# Mezz2.net
KiCad netlist of a schematic drawn in Altium Designer
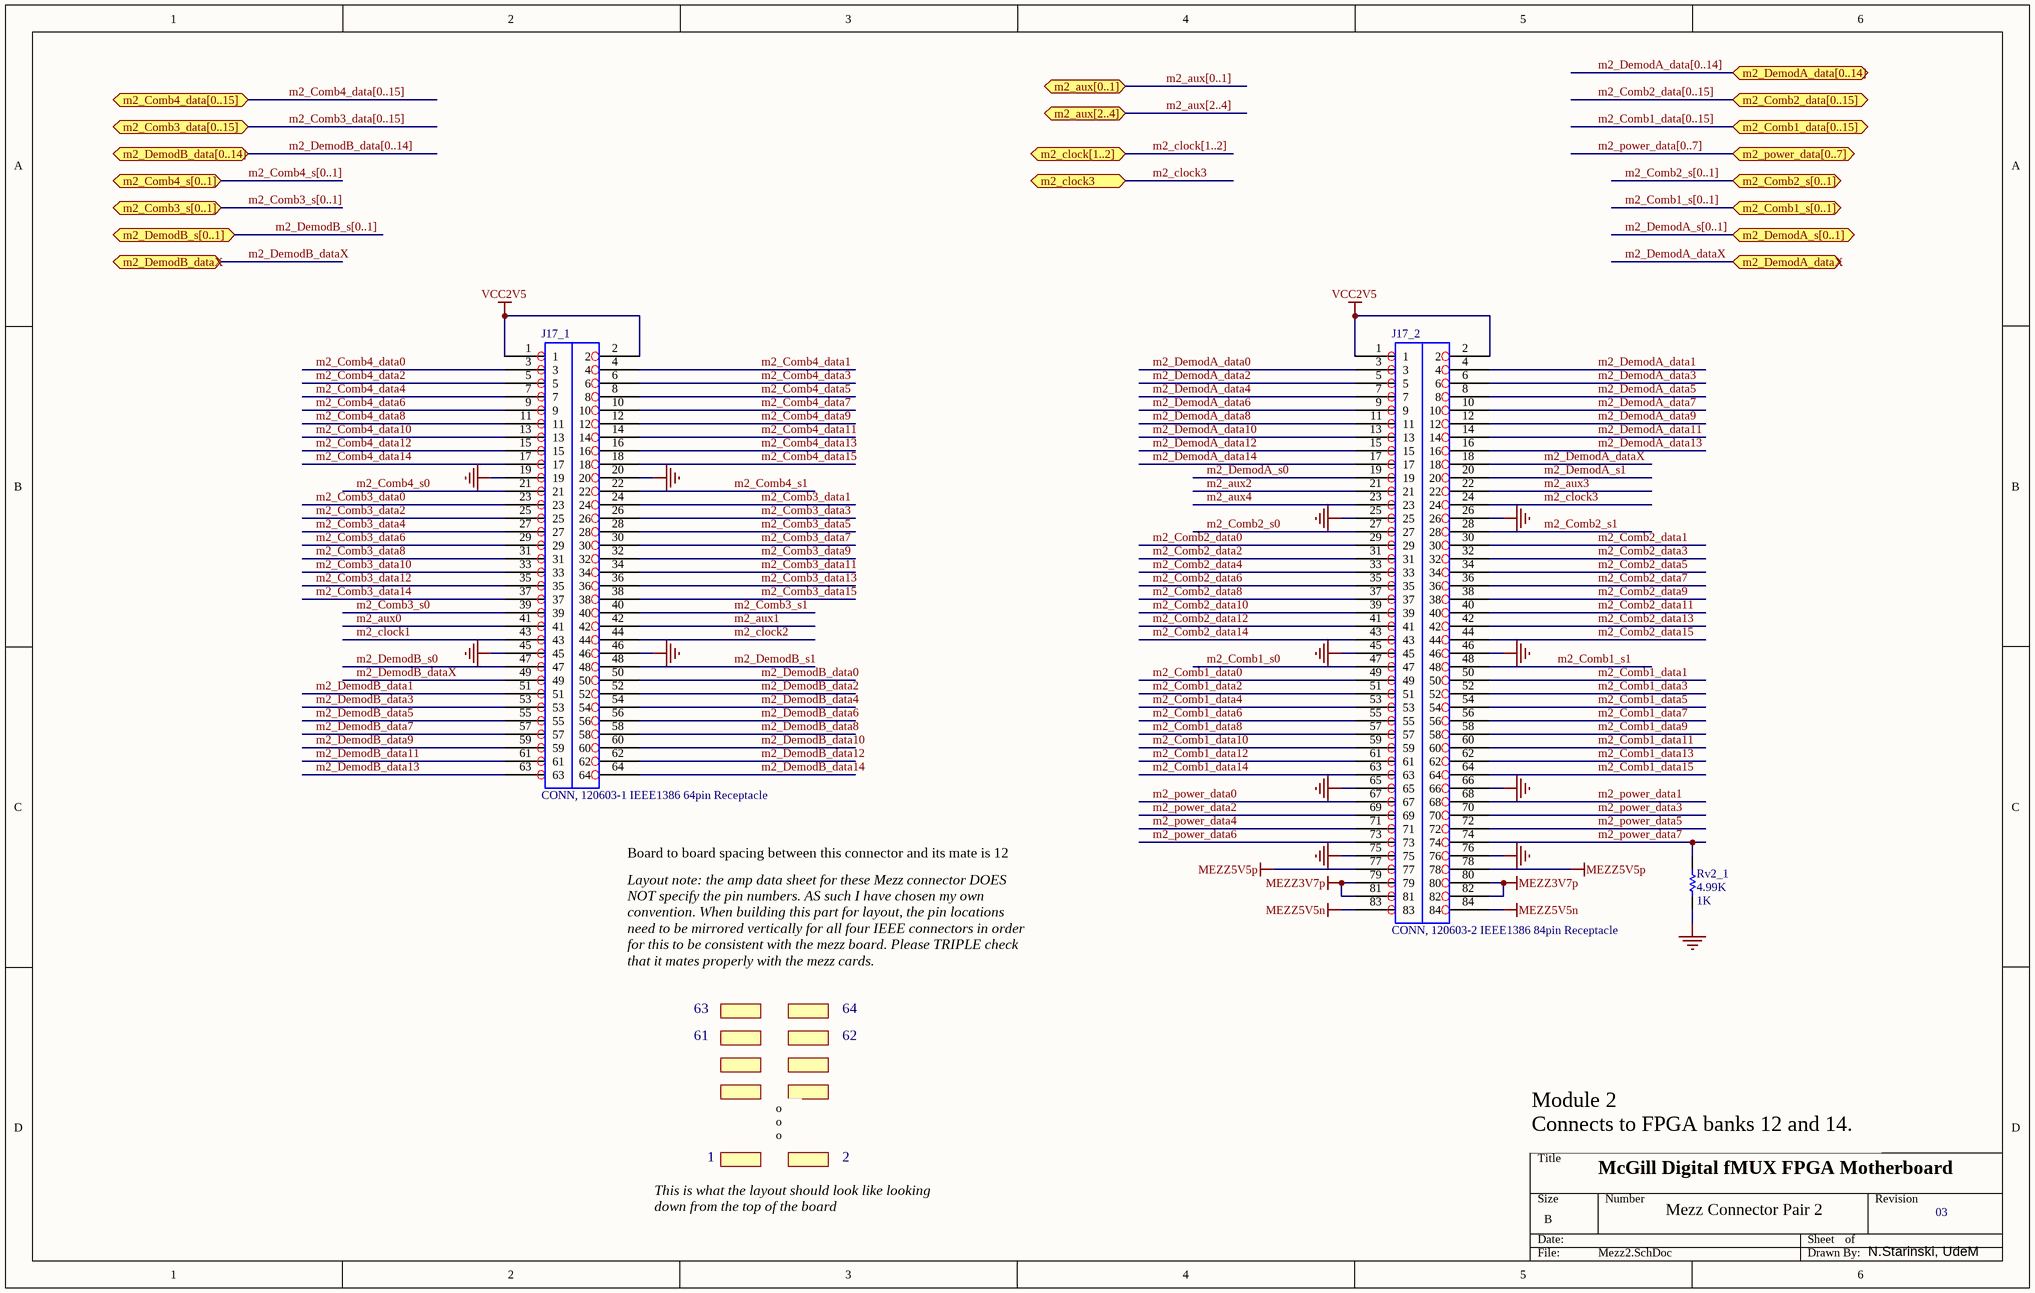
[diagram p0: Mezz2.SchDoc]

(export (version "E")
  (design (tool "Eeschema 10.0.6"))
  (components
    (comp (ref "J17_1")
      (value "CONN, 120603-1 IEEE1386 64pin Receptacle")
      (footprint "120603-1")
      (description "1.0mm FH (IEEE1386) 64-pin Connector")
      (libsource (lib "IEEE1386") (part "120603-1"))
    )
    (comp (ref "J17_2")
      (value "CONN, 120603-2 IEEE1386 84pin Receptacle")
      (footprint "120603-2")
      (description "1.0mm FH (IEEE1386) 84-pin Connector")
      (libsource (lib "IEEE1386") (part "120603-2"))
    )
    (comp (ref "Rv2_1")
      (value "4.99K")
      (footprint "1608[0603]")
      (description "Semiconductor Resistor")
      (fields (field (name "ALTIUM_VALUE") "1K") (field (name "PUBLISHER") "Altium Limited"))
      (libsource (lib "Miscellaneous Devices") (part "Res Semi"))
    )
  )
  (nets
    (net (code "1") (name "/m2_Comb1_data0") (class "Default")
      (node (ref "J17_2") (pin "49") (pinfunction "49_49") (pintype "passive"))
    )
    (net (code "2") (name "/m2_Comb1_data1") (class "Default")
      (node (ref "J17_2") (pin "50") (pinfunction "50_50") (pintype "passive"))
    )
    (net (code "3") (name "/m2_Comb1_data2") (class "Default")
      (node (ref "J17_2") (pin "51") (pinfunction "51_51") (pintype "passive"))
    )
    (net (code "4") (name "/m2_Comb1_data3") (class "Default")
      (node (ref "J17_2") (pin "52") (pinfunction "52_52") (pintype "passive"))
    )
    (net (code "5") (name "/m2_Comb1_data4") (class "Default")
      (node (ref "J17_2") (pin "53") (pinfunction "53_53") (pintype "passive"))
    )
    (net (code "6") (name "/m2_Comb1_data5") (class "Default")
      (node (ref "J17_2") (pin "54") (pinfunction "54_54") (pintype "passive"))
    )
    (net (code "7") (name "/m2_Comb1_data6") (class "Default")
      (node (ref "J17_2") (pin "55") (pinfunction "55_55") (pintype "passive"))
    )
    (net (code "8") (name "/m2_Comb1_data7") (class "Default")
      (node (ref "J17_2") (pin "56") (pinfunction "56_56") (pintype "passive"))
    )
    (net (code "9") (name "/m2_Comb1_data8") (class "Default")
      (node (ref "J17_2") (pin "57") (pinfunction "57_57") (pintype "passive"))
    )
    (net (code "10") (name "/m2_Comb1_data9") (class "Default")
      (node (ref "J17_2") (pin "58") (pinfunction "58_58") (pintype "passive"))
    )
    (net (code "11") (name "/m2_Comb1_data10") (class "Default")
      (node (ref "J17_2") (pin "59") (pinfunction "59_59") (pintype "passive"))
    )
    (net (code "12") (name "/m2_Comb1_data11") (class "Default")
      (node (ref "J17_2") (pin "60") (pinfunction "60_60") (pintype "passive"))
    )
    (net (code "13") (name "/m2_Comb1_data12") (class "Default")
      (node (ref "J17_2") (pin "61") (pinfunction "61_61") (pintype "passive"))
    )
    (net (code "14") (name "/m2_Comb1_data13") (class "Default")
      (node (ref "J17_2") (pin "62") (pinfunction "62_62") (pintype "passive"))
    )
    (net (code "15") (name "/m2_Comb1_data14") (class "Default")
      (node (ref "J17_2") (pin "63") (pinfunction "63_63") (pintype "passive"))
    )
    (net (code "16") (name "/m2_Comb1_data15") (class "Default")
      (node (ref "J17_2") (pin "64") (pinfunction "64_64") (pintype "passive"))
    )
    (net (code "18") (name "/m2_Comb1_s0") (class "Default")
      (node (ref "J17_2") (pin "47") (pinfunction "47_47") (pintype "passive"))
    )
    (net (code "19") (name "/m2_Comb1_s1") (class "Default")
      (node (ref "J17_2") (pin "48") (pinfunction "48_48") (pintype "passive"))
    )
    (net (code "21") (name "/m2_Comb2_data0") (class "Default")
      (node (ref "J17_2") (pin "29") (pinfunction "29_29") (pintype "passive"))
    )
    (net (code "22") (name "/m2_Comb2_data1") (class "Default")
      (node (ref "J17_2") (pin "30") (pinfunction "30_30") (pintype "passive"))
    )
    (net (code "23") (name "/m2_Comb2_data2") (class "Default")
      (node (ref "J17_2") (pin "31") (pinfunction "31_31") (pintype "passive"))
    )
    (net (code "24") (name "/m2_Comb2_data3") (class "Default")
      (node (ref "J17_2") (pin "32") (pinfunction "32_32") (pintype "passive"))
    )
    (net (code "25") (name "/m2_Comb2_data4") (class "Default")
      (node (ref "J17_2") (pin "33") (pinfunction "33_33") (pintype "passive"))
    )
    (net (code "26") (name "/m2_Comb2_data5") (class "Default")
      (node (ref "J17_2") (pin "34") (pinfunction "34_34") (pintype "passive"))
    )
    (net (code "27") (name "/m2_Comb2_data6") (class "Default")
      (node (ref "J17_2") (pin "35") (pinfunction "35_35") (pintype "passive"))
    )
    (net (code "28") (name "/m2_Comb2_data7") (class "Default")
      (node (ref "J17_2") (pin "36") (pinfunction "36_36") (pintype "passive"))
    )
    (net (code "29") (name "/m2_Comb2_data8") (class "Default")
      (node (ref "J17_2") (pin "37") (pinfunction "37_37") (pintype "passive"))
    )
    (net (code "30") (name "/m2_Comb2_data9") (class "Default")
      (node (ref "J17_2") (pin "38") (pinfunction "38_38") (pintype "passive"))
    )
    (net (code "31") (name "/m2_Comb2_data10") (class "Default")
      (node (ref "J17_2") (pin "39") (pinfunction "39_39") (pintype "passive"))
    )
    (net (code "32") (name "/m2_Comb2_data11") (class "Default")
      (node (ref "J17_2") (pin "40") (pinfunction "40_40") (pintype "passive"))
    )
    (net (code "33") (name "/m2_Comb2_data12") (class "Default")
      (node (ref "J17_2") (pin "41") (pinfunction "41_41") (pintype "passive"))
    )
    (net (code "34") (name "/m2_Comb2_data13") (class "Default")
      (node (ref "J17_2") (pin "42") (pinfunction "42_42") (pintype "passive"))
    )
    (net (code "35") (name "/m2_Comb2_data14") (class "Default")
      (node (ref "J17_2") (pin "43") (pinfunction "43_43") (pintype "passive"))
    )
    (net (code "36") (name "/m2_Comb2_data15") (class "Default")
      (node (ref "J17_2") (pin "44") (pinfunction "44_44") (pintype "passive"))
    )
    (net (code "38") (name "/m2_Comb2_s0") (class "Default")
      (node (ref "J17_2") (pin "27") (pinfunction "27_27") (pintype "passive"))
    )
    (net (code "39") (name "/m2_Comb2_s1") (class "Default")
      (node (ref "J17_2") (pin "28") (pinfunction "28_28") (pintype "passive"))
    )
    (net (code "41") (name "/m2_Comb3_data0") (class "Default")
      (node (ref "J17_1") (pin "23") (pinfunction "23_23") (pintype "passive"))
    )
    (net (code "42") (name "/m2_Comb3_data1") (class "Default")
      (node (ref "J17_1") (pin "24") (pinfunction "24_24") (pintype "passive"))
    )
    (net (code "43") (name "/m2_Comb3_data2") (class "Default")
      (node (ref "J17_1") (pin "25") (pinfunction "25_25") (pintype "passive"))
    )
    (net (code "44") (name "/m2_Comb3_data3") (class "Default")
      (node (ref "J17_1") (pin "26") (pinfunction "26_26") (pintype "passive"))
    )
    (net (code "45") (name "/m2_Comb3_data4") (class "Default")
      (node (ref "J17_1") (pin "27") (pinfunction "27_27") (pintype "passive"))
    )
    (net (code "46") (name "/m2_Comb3_data5") (class "Default")
      (node (ref "J17_1") (pin "28") (pinfunction "28_28") (pintype "passive"))
    )
    (net (code "47") (name "/m2_Comb3_data6") (class "Default")
      (node (ref "J17_1") (pin "29") (pinfunction "29_29") (pintype "passive"))
    )
    (net (code "48") (name "/m2_Comb3_data7") (class "Default")
      (node (ref "J17_1") (pin "30") (pinfunction "30_30") (pintype "passive"))
    )
    (net (code "49") (name "/m2_Comb3_data8") (class "Default")
      (node (ref "J17_1") (pin "31") (pinfunction "31_31") (pintype "passive"))
    )
    (net (code "50") (name "/m2_Comb3_data9") (class "Default")
      (node (ref "J17_1") (pin "32") (pinfunction "32_32") (pintype "passive"))
    )
    (net (code "51") (name "/m2_Comb3_data10") (class "Default")
      (node (ref "J17_1") (pin "33") (pinfunction "33_33") (pintype "passive"))
    )
    (net (code "52") (name "/m2_Comb3_data11") (class "Default")
      (node (ref "J17_1") (pin "34") (pinfunction "34_34") (pintype "passive"))
    )
    (net (code "53") (name "/m2_Comb3_data12") (class "Default")
      (node (ref "J17_1") (pin "35") (pinfunction "35_35") (pintype "passive"))
    )
    (net (code "54") (name "/m2_Comb3_data13") (class "Default")
      (node (ref "J17_1") (pin "36") (pinfunction "36_36") (pintype "passive"))
    )
    (net (code "55") (name "/m2_Comb3_data14") (class "Default")
      (node (ref "J17_1") (pin "37") (pinfunction "37_37") (pintype "passive"))
    )
    (net (code "56") (name "/m2_Comb3_data15") (class "Default")
      (node (ref "J17_1") (pin "38") (pinfunction "38_38") (pintype "passive"))
    )
    (net (code "58") (name "/m2_Comb3_s0") (class "Default")
      (node (ref "J17_1") (pin "39") (pinfunction "39_39") (pintype "passive"))
    )
    (net (code "59") (name "/m2_Comb3_s1") (class "Default")
      (node (ref "J17_1") (pin "40") (pinfunction "40_40") (pintype "passive"))
    )
    (net (code "61") (name "/m2_Comb4_data0") (class "Default")
      (node (ref "J17_1") (pin "3") (pinfunction "3_3") (pintype "passive"))
    )
    (net (code "62") (name "/m2_Comb4_data1") (class "Default")
      (node (ref "J17_1") (pin "4") (pinfunction "4_4") (pintype "passive"))
    )
    (net (code "63") (name "/m2_Comb4_data2") (class "Default")
      (node (ref "J17_1") (pin "5") (pinfunction "5_5") (pintype "passive"))
    )
    (net (code "64") (name "/m2_Comb4_data3") (class "Default")
      (node (ref "J17_1") (pin "6") (pinfunction "6_6") (pintype "passive"))
    )
    (net (code "65") (name "/m2_Comb4_data4") (class "Default")
      (node (ref "J17_1") (pin "7") (pinfunction "7_7") (pintype "passive"))
    )
    (net (code "66") (name "/m2_Comb4_data5") (class "Default")
      (node (ref "J17_1") (pin "8") (pinfunction "8_8") (pintype "passive"))
    )
    (net (code "67") (name "/m2_Comb4_data6") (class "Default")
      (node (ref "J17_1") (pin "9") (pinfunction "9_9") (pintype "passive"))
    )
    (net (code "68") (name "/m2_Comb4_data7") (class "Default")
      (node (ref "J17_1") (pin "10") (pinfunction "10_10") (pintype "passive"))
    )
    (net (code "69") (name "/m2_Comb4_data8") (class "Default")
      (node (ref "J17_1") (pin "11") (pinfunction "11_11") (pintype "passive"))
    )
    (net (code "70") (name "/m2_Comb4_data9") (class "Default")
      (node (ref "J17_1") (pin "12") (pinfunction "12_12") (pintype "passive"))
    )
    (net (code "71") (name "/m2_Comb4_data10") (class "Default")
      (node (ref "J17_1") (pin "13") (pinfunction "13_13") (pintype "passive"))
    )
    (net (code "72") (name "/m2_Comb4_data11") (class "Default")
      (node (ref "J17_1") (pin "14") (pinfunction "14_14") (pintype "passive"))
    )
    (net (code "73") (name "/m2_Comb4_data12") (class "Default")
      (node (ref "J17_1") (pin "15") (pinfunction "15_15") (pintype "passive"))
    )
    (net (code "74") (name "/m2_Comb4_data13") (class "Default")
      (node (ref "J17_1") (pin "16") (pinfunction "16_16") (pintype "passive"))
    )
    (net (code "75") (name "/m2_Comb4_data14") (class "Default")
      (node (ref "J17_1") (pin "17") (pinfunction "17_17") (pintype "passive"))
    )
    (net (code "76") (name "/m2_Comb4_data15") (class "Default")
      (node (ref "J17_1") (pin "18") (pinfunction "18_18") (pintype "passive"))
    )
    (net (code "78") (name "/m2_Comb4_s0") (class "Default")
      (node (ref "J17_1") (pin "21") (pinfunction "21_21") (pintype "passive"))
    )
    (net (code "79") (name "/m2_Comb4_s1") (class "Default")
      (node (ref "J17_1") (pin "22") (pinfunction "22_22") (pintype "passive"))
    )
    (net (code "81") (name "/m2_DemodA_data0") (class "Default")
      (node (ref "J17_2") (pin "3") (pinfunction "3_3") (pintype "passive"))
    )
    (net (code "82") (name "/m2_DemodA_data1") (class "Default")
      (node (ref "J17_2") (pin "4") (pinfunction "4_4") (pintype "passive"))
    )
    (net (code "83") (name "/m2_DemodA_data2") (class "Default")
      (node (ref "J17_2") (pin "5") (pinfunction "5_5") (pintype "passive"))
    )
    (net (code "84") (name "/m2_DemodA_data3") (class "Default")
      (node (ref "J17_2") (pin "6") (pinfunction "6_6") (pintype "passive"))
    )
    (net (code "85") (name "/m2_DemodA_data4") (class "Default")
      (node (ref "J17_2") (pin "7") (pinfunction "7_7") (pintype "passive"))
    )
    (net (code "86") (name "/m2_DemodA_data5") (class "Default")
      (node (ref "J17_2") (pin "8") (pinfunction "8_8") (pintype "passive"))
    )
    (net (code "87") (name "/m2_DemodA_data6") (class "Default")
      (node (ref "J17_2") (pin "9") (pinfunction "9_9") (pintype "passive"))
    )
    (net (code "88") (name "/m2_DemodA_data7") (class "Default")
      (node (ref "J17_2") (pin "10") (pinfunction "10_10") (pintype "passive"))
    )
    (net (code "89") (name "/m2_DemodA_data8") (class "Default")
      (node (ref "J17_2") (pin "11") (pinfunction "11_11") (pintype "passive"))
    )
    (net (code "90") (name "/m2_DemodA_data9") (class "Default")
      (node (ref "J17_2") (pin "12") (pinfunction "12_12") (pintype "passive"))
    )
    (net (code "91") (name "/m2_DemodA_data10") (class "Default")
      (node (ref "J17_2") (pin "13") (pinfunction "13_13") (pintype "passive"))
    )
    (net (code "92") (name "/m2_DemodA_data11") (class "Default")
      (node (ref "J17_2") (pin "14") (pinfunction "14_14") (pintype "passive"))
    )
    (net (code "93") (name "/m2_DemodA_data12") (class "Default")
      (node (ref "J17_2") (pin "15") (pinfunction "15_15") (pintype "passive"))
    )
    (net (code "94") (name "/m2_DemodA_data13") (class "Default")
      (node (ref "J17_2") (pin "16") (pinfunction "16_16") (pintype "passive"))
    )
    (net (code "95") (name "/m2_DemodA_data14") (class "Default")
      (node (ref "J17_2") (pin "17") (pinfunction "17_17") (pintype "passive"))
    )
    (net (code "96") (name "/m2_DemodA_dataX") (class "Default")
      (node (ref "J17_2") (pin "18") (pinfunction "18_18") (pintype "passive"))
    )
    (net (code "98") (name "/m2_DemodA_s0") (class "Default")
      (node (ref "J17_2") (pin "19") (pinfunction "19_19") (pintype "passive"))
    )
    (net (code "99") (name "/m2_DemodA_s1") (class "Default")
      (node (ref "J17_2") (pin "20") (pinfunction "20_20") (pintype "passive"))
    )
    (net (code "101") (name "/m2_DemodB_data0") (class "Default")
      (node (ref "J17_1") (pin "50") (pinfunction "50_50") (pintype "passive"))
    )
    (net (code "102") (name "/m2_DemodB_data1") (class "Default")
      (node (ref "J17_1") (pin "51") (pinfunction "51_51") (pintype "passive"))
    )
    (net (code "103") (name "/m2_DemodB_data2") (class "Default")
      (node (ref "J17_1") (pin "52") (pinfunction "52_52") (pintype "passive"))
    )
    (net (code "104") (name "/m2_DemodB_data3") (class "Default")
      (node (ref "J17_1") (pin "53") (pinfunction "53_53") (pintype "passive"))
    )
    (net (code "105") (name "/m2_DemodB_data4") (class "Default")
      (node (ref "J17_1") (pin "54") (pinfunction "54_54") (pintype "passive"))
    )
    (net (code "106") (name "/m2_DemodB_data5") (class "Default")
      (node (ref "J17_1") (pin "55") (pinfunction "55_55") (pintype "passive"))
    )
    (net (code "107") (name "/m2_DemodB_data6") (class "Default")
      (node (ref "J17_1") (pin "56") (pinfunction "56_56") (pintype "passive"))
    )
    (net (code "108") (name "/m2_DemodB_data7") (class "Default")
      (node (ref "J17_1") (pin "57") (pinfunction "57_57") (pintype "passive"))
    )
    (net (code "109") (name "/m2_DemodB_data8") (class "Default")
      (node (ref "J17_1") (pin "58") (pinfunction "58_58") (pintype "passive"))
    )
    (net (code "110") (name "/m2_DemodB_data9") (class "Default")
      (node (ref "J17_1") (pin "59") (pinfunction "59_59") (pintype "passive"))
    )
    (net (code "111") (name "/m2_DemodB_data10") (class "Default")
      (node (ref "J17_1") (pin "60") (pinfunction "60_60") (pintype "passive"))
    )
    (net (code "112") (name "/m2_DemodB_data11") (class "Default")
      (node (ref "J17_1") (pin "61") (pinfunction "61_61") (pintype "passive"))
    )
    (net (code "113") (name "/m2_DemodB_data12") (class "Default")
      (node (ref "J17_1") (pin "62") (pinfunction "62_62") (pintype "passive"))
    )
    (net (code "114") (name "/m2_DemodB_data13") (class "Default")
      (node (ref "J17_1") (pin "63") (pinfunction "63_63") (pintype "passive"))
    )
    (net (code "115") (name "/m2_DemodB_data14") (class "Default")
      (node (ref "J17_1") (pin "64") (pinfunction "64_64") (pintype "passive"))
    )
    (net (code "116") (name "/m2_DemodB_dataX") (class "Default")
      (node (ref "J17_1") (pin "49") (pinfunction "49_49") (pintype "passive"))
    )
    (net (code "118") (name "/m2_DemodB_s0") (class "Default")
      (node (ref "J17_1") (pin "47") (pinfunction "47_47") (pintype "passive"))
    )
    (net (code "119") (name "/m2_DemodB_s1") (class "Default")
      (node (ref "J17_1") (pin "48") (pinfunction "48_48") (pintype "passive"))
    )
    (net (code "121") (name "/m2_aux0") (class "Default")
      (node (ref "J17_1") (pin "41") (pinfunction "41_41") (pintype "passive"))
    )
    (net (code "122") (name "/m2_aux1") (class "Default")
      (node (ref "J17_1") (pin "42") (pinfunction "42_42") (pintype "passive"))
    )
    (net (code "123") (name "/m2_aux2") (class "Default")
      (node (ref "J17_2") (pin "21") (pinfunction "21_21") (pintype "passive"))
    )
    (net (code "124") (name "/m2_aux3") (class "Default")
      (node (ref "J17_2") (pin "22") (pinfunction "22_22") (pintype "passive"))
    )
    (net (code "125") (name "/m2_aux4") (class "Default")
      (node (ref "J17_2") (pin "23") (pinfunction "23_23") (pintype "passive"))
    )
    (net (code "128") (name "/m2_clock1") (class "Default")
      (node (ref "J17_1") (pin "43") (pinfunction "43_43") (pintype "passive"))
    )
    (net (code "129") (name "/m2_clock2") (class "Default")
      (node (ref "J17_1") (pin "44") (pinfunction "44_44") (pintype "passive"))
    )
    (net (code "130") (name "/m2_clock3") (class "Default")
      (node (ref "J17_2") (pin "24") (pinfunction "24_24") (pintype "passive"))
    )
    (net (code "132") (name "/m2_power_data0") (class "Default")
      (node (ref "J17_2") (pin "67") (pinfunction "67_67") (pintype "passive"))
    )
    (net (code "133") (name "/m2_power_data1") (class "Default")
      (node (ref "J17_2") (pin "68") (pinfunction "68_68") (pintype "passive"))
    )
    (net (code "134") (name "/m2_power_data2") (class "Default")
      (node (ref "J17_2") (pin "69") (pinfunction "69_69") (pintype "passive"))
    )
    (net (code "135") (name "/m2_power_data3") (class "Default")
      (node (ref "J17_2") (pin "70") (pinfunction "70_70") (pintype "passive"))
    )
    (net (code "136") (name "/m2_power_data4") (class "Default")
      (node (ref "J17_2") (pin "71") (pinfunction "71_71") (pintype "passive"))
    )
    (net (code "137") (name "/m2_power_data5") (class "Default")
      (node (ref "J17_2") (pin "72") (pinfunction "72_72") (pintype "passive"))
    )
    (net (code "138") (name "/m2_power_data6") (class "Default")
      (node (ref "J17_2") (pin "73") (pinfunction "73_73") (pintype "passive"))
    )
    (net (code "139") (name "/m2_power_data7") (class "Default")
      (node (ref "J17_2") (pin "74") (pinfunction "74_74") (pintype "passive"))
      (node (ref "Rv2_1") (pin "2") (pinfunction "2_2") (pintype "passive"))
    )
    (net (code "141") (name "GND") (class "Default")
      (node (ref "J17_1") (pin "19") (pinfunction "19_19") (pintype "passive"))
      (node (ref "J17_1") (pin "20") (pinfunction "20_20") (pintype "passive"))
      (node (ref "J17_1") (pin "45") (pinfunction "45_45") (pintype "passive"))
      (node (ref "J17_1") (pin "46") (pinfunction "46_46") (pintype "passive"))
      (node (ref "J17_2") (pin "25") (pinfunction "25_25") (pintype "passive"))
      (node (ref "J17_2") (pin "26") (pinfunction "26_26") (pintype "passive"))
      (node (ref "J17_2") (pin "45") (pinfunction "45_45") (pintype "passive"))
      (node (ref "J17_2") (pin "46") (pinfunction "46_46") (pintype "passive"))
      (node (ref "J17_2") (pin "65") (pinfunction "65_65") (pintype "passive"))
      (node (ref "J17_2") (pin "66") (pinfunction "66_66") (pintype "passive"))
      (node (ref "J17_2") (pin "75") (pinfunction "75_75") (pintype "passive"))
      (node (ref "J17_2") (pin "76") (pinfunction "76_76") (pintype "passive"))
      (node (ref "Rv2_1") (pin "1") (pinfunction "1_1") (pintype "passive"))
    )
    (net (code "142") (name "MEZZ3V7p") (class "Default")
      (node (ref "J17_2") (pin "79") (pinfunction "79_79") (pintype "passive"))
      (node (ref "J17_2") (pin "80") (pinfunction "80_80") (pintype "passive"))
      (node (ref "J17_2") (pin "81") (pinfunction "81_81") (pintype "passive"))
      (node (ref "J17_2") (pin "82") (pinfunction "82_82") (pintype "passive"))
    )
    (net (code "143") (name "MEZZ5V5n") (class "Default")
      (node (ref "J17_2") (pin "83") (pinfunction "83_83") (pintype "passive"))
      (node (ref "J17_2") (pin "84") (pinfunction "84_84") (pintype "passive"))
    )
    (net (code "144") (name "MEZZ5V5p") (class "Default")
      (node (ref "J17_2") (pin "77") (pinfunction "77_77") (pintype "passive"))
      (node (ref "J17_2") (pin "78") (pinfunction "78_78") (pintype "passive"))
    )
    (net (code "145") (name "VCC2V5") (class "Default")
      (node (ref "J17_1") (pin "1") (pinfunction "1_1") (pintype "passive"))
      (node (ref "J17_1") (pin "2") (pinfunction "2_2") (pintype "passive"))
      (node (ref "J17_2") (pin "1") (pinfunction "1_1") (pintype "passive"))
      (node (ref "J17_2") (pin "2") (pinfunction "2_2") (pintype "passive"))
    )
  )
)
